# withcc3200.net
KiCad netlist of a schematic drawn in EAGLE
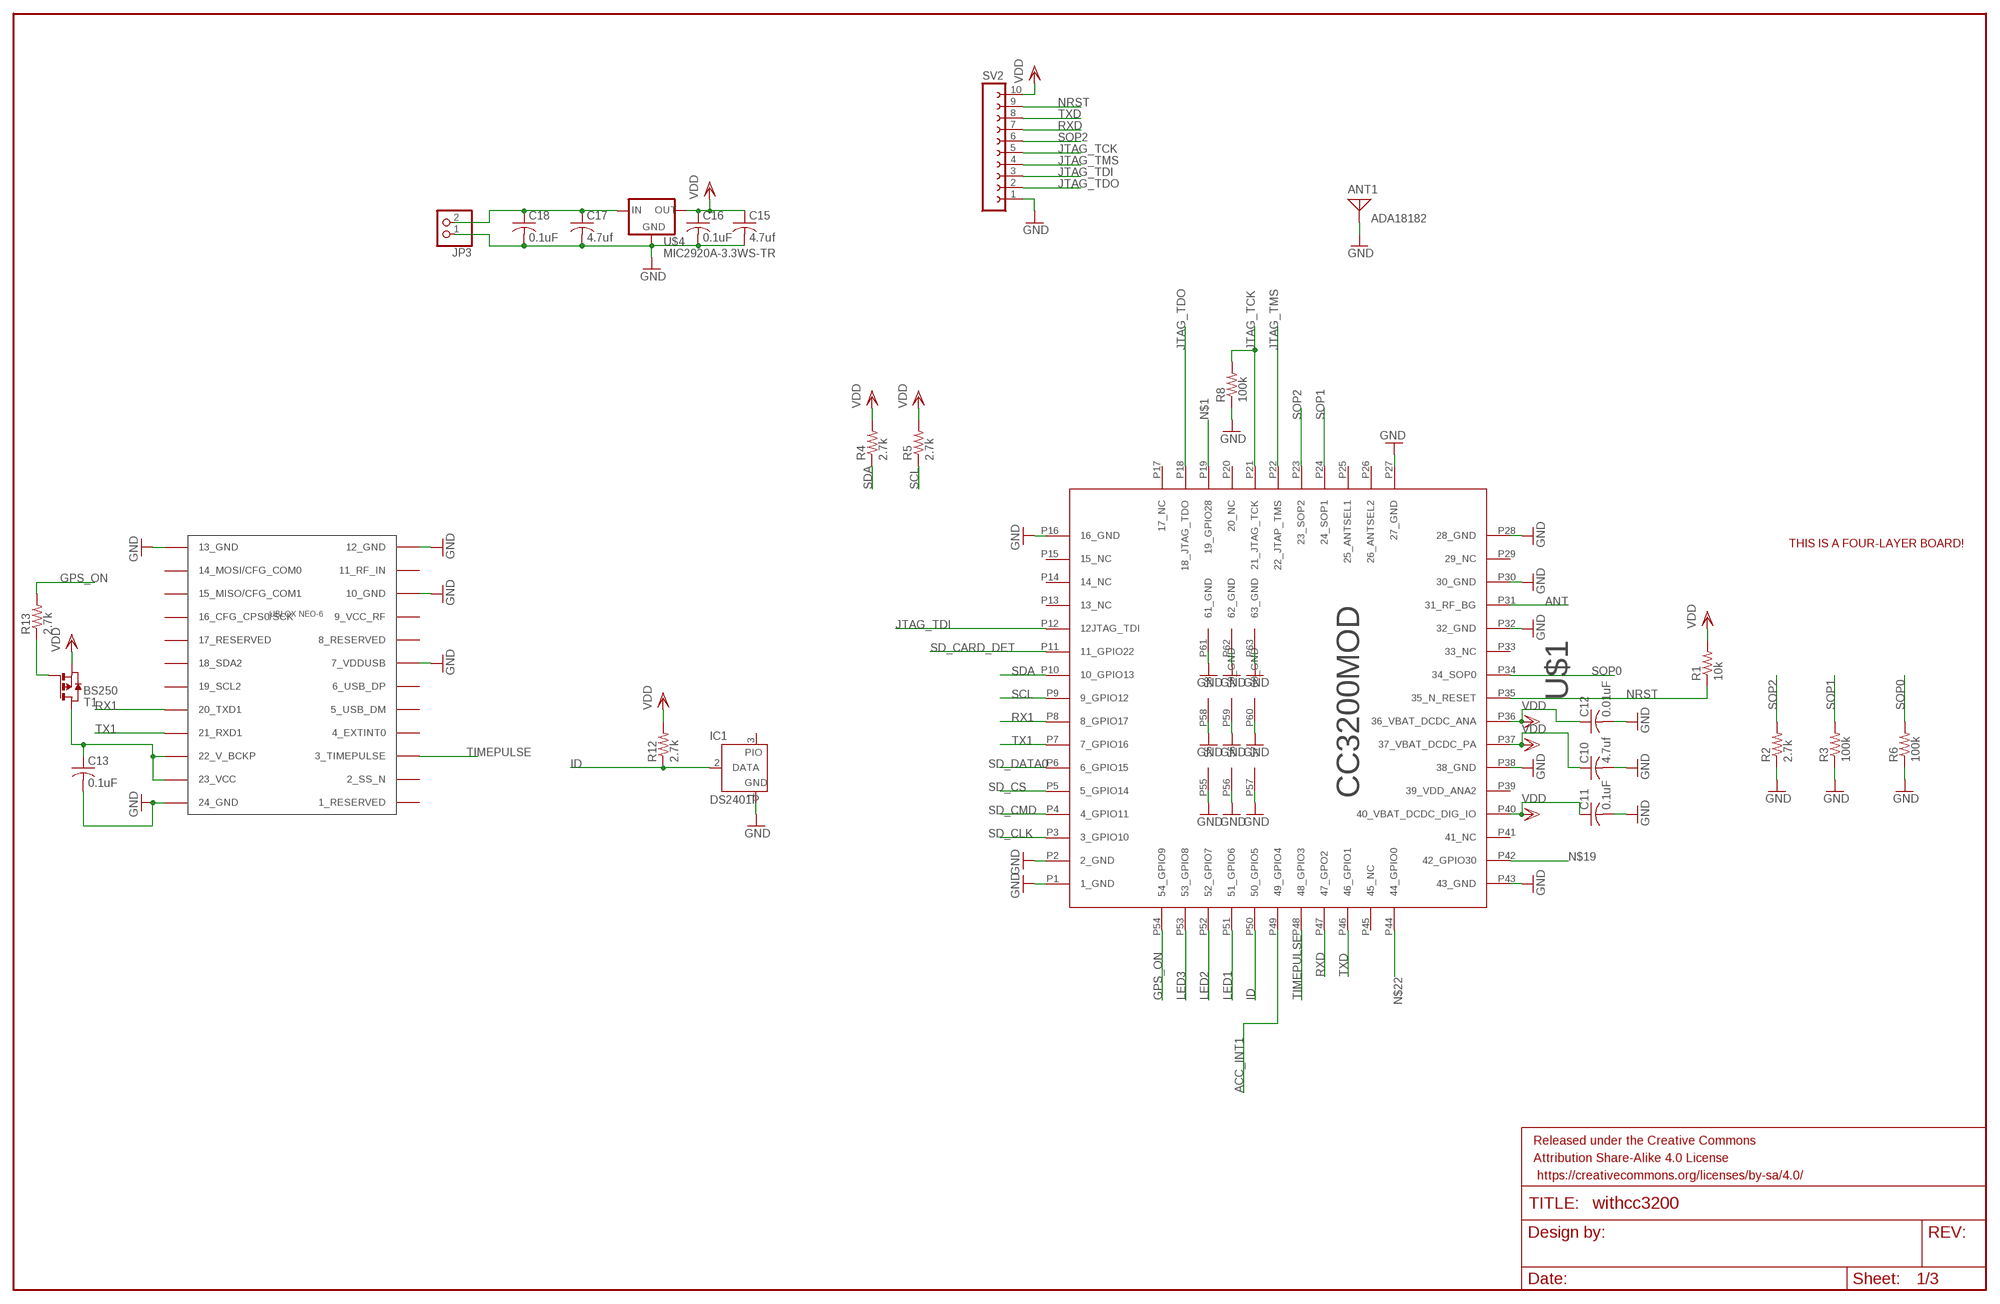
[diagram p0: schematic, sheet 1]
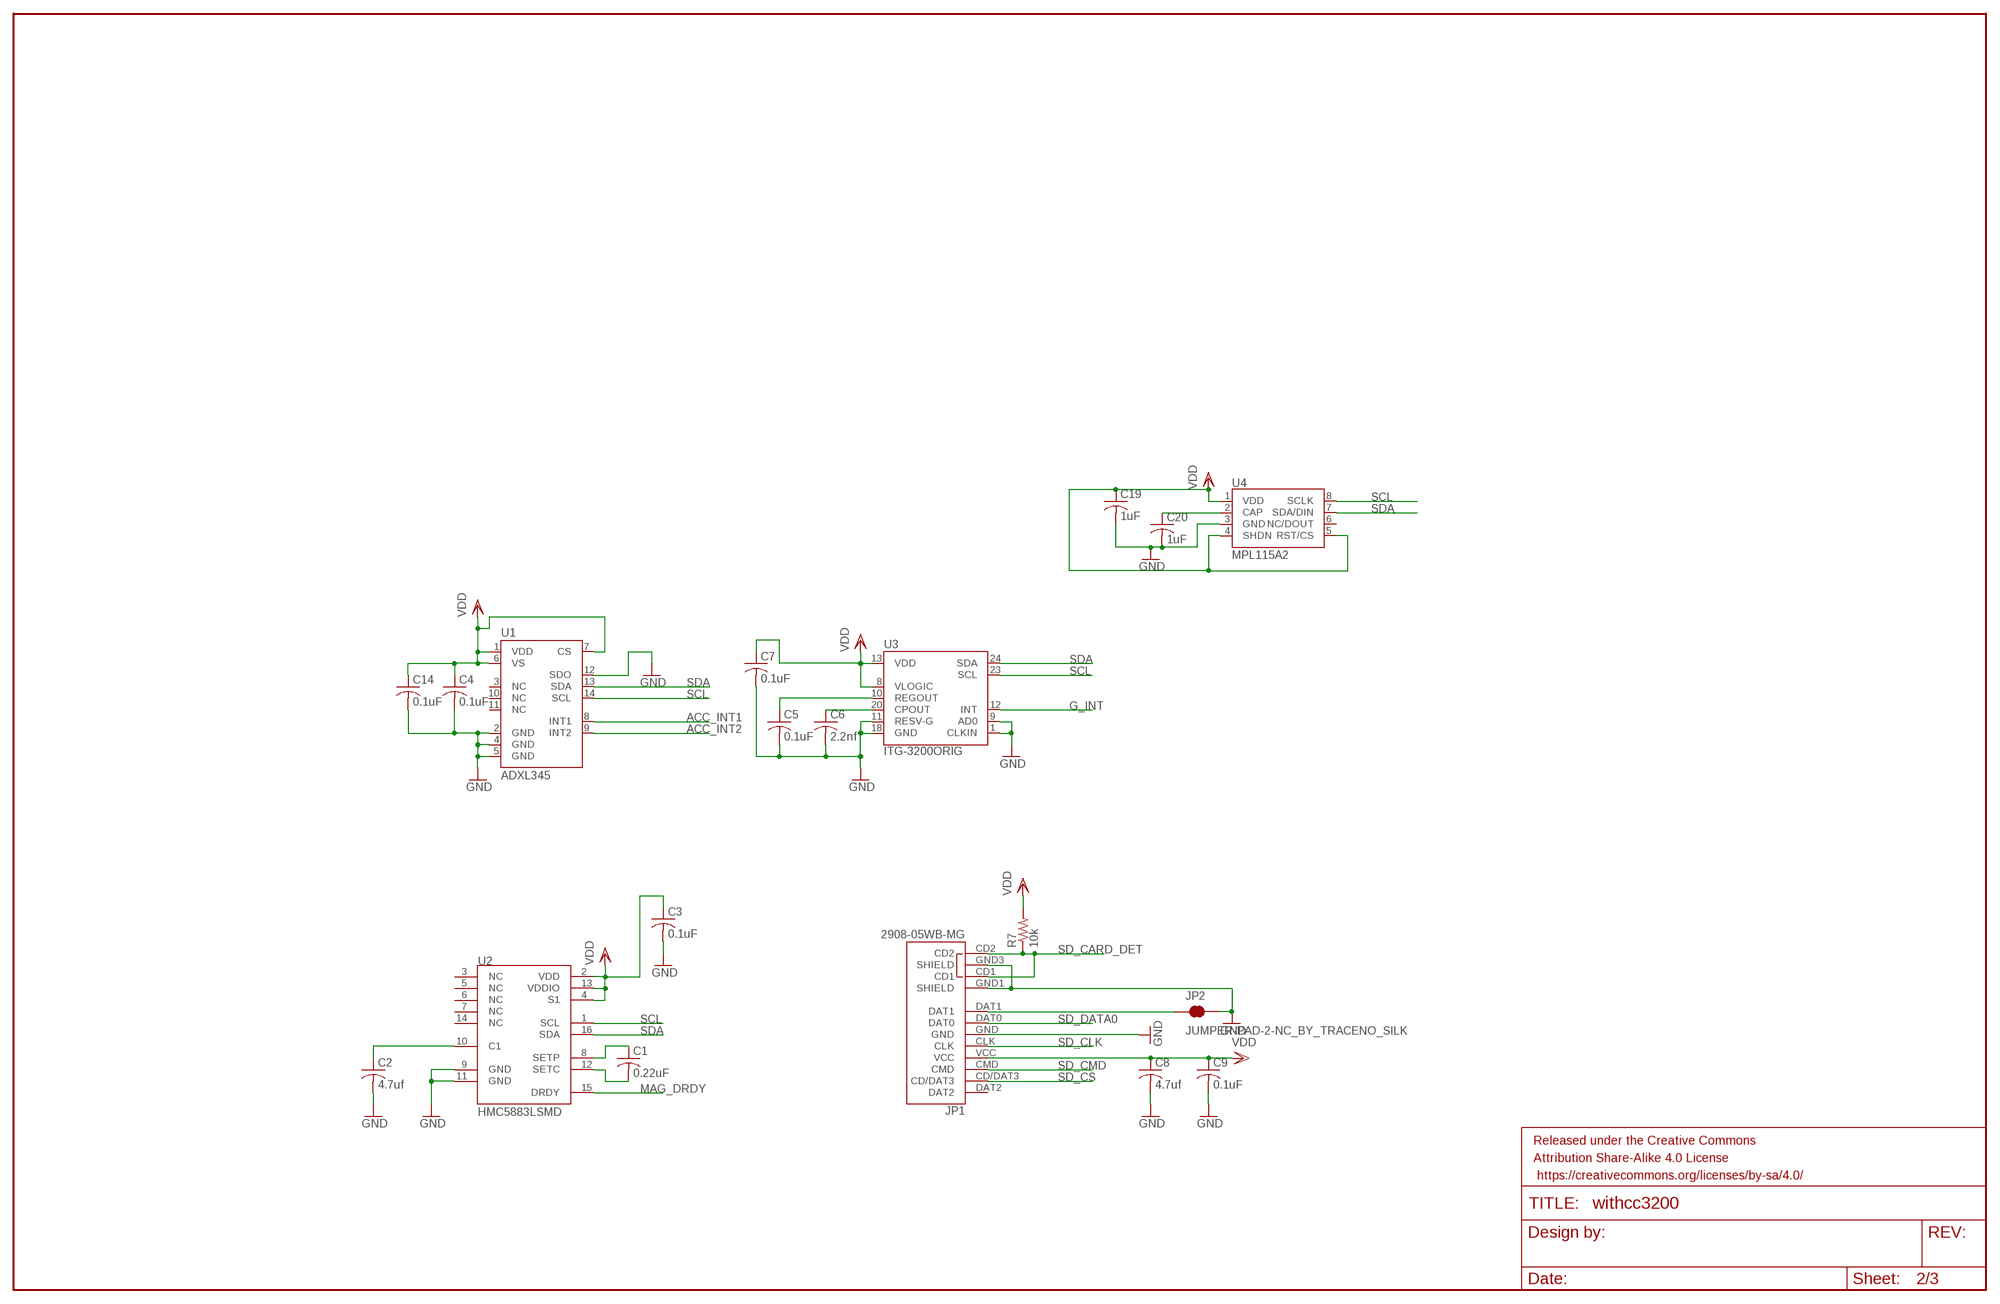
[diagram p1: schematic, sheet 2]
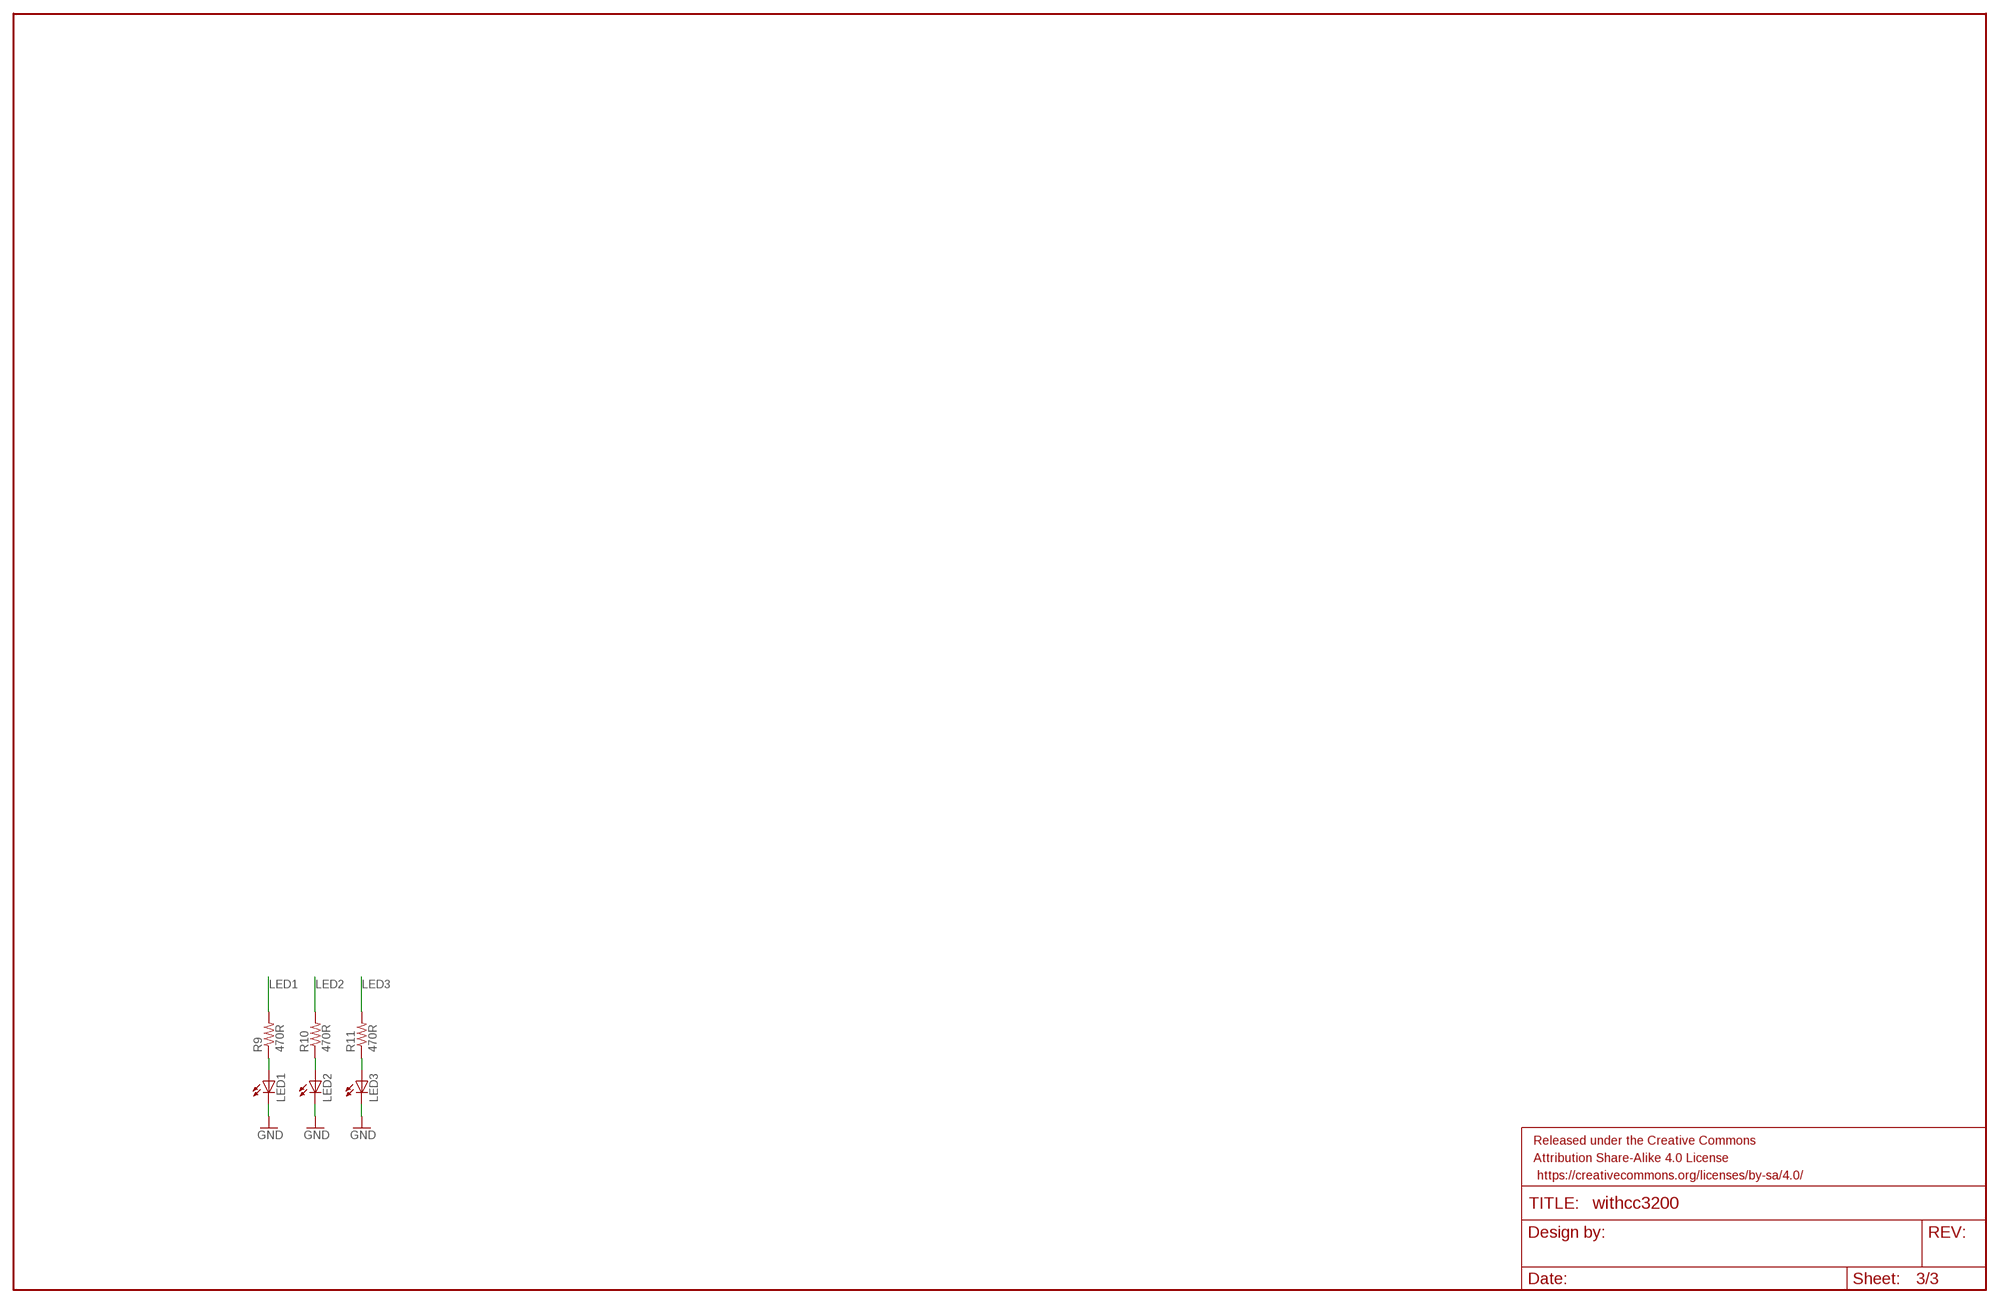
[diagram p2: schematic, sheet 3]

(export (version "E")
  (design (tool "Eeschema 10.0.6"))
  (components
    (comp (ref "C1")
      (value "0.22uF")
      (footprint "eagle-import:C0805K")
      (libsource (lib "eagle-import") (part "C-USC0805K"))
    )
    (comp (ref "C2")
      (value "4.7uf")
      (footprint "eagle-import:C0805K")
      (libsource (lib "eagle-import") (part "C-USC0805K"))
    )
    (comp (ref "C3")
      (value "0.1uF")
      (footprint "eagle-import:C0805K")
      (libsource (lib "eagle-import") (part "C-USC0805K"))
    )
    (comp (ref "C4")
      (value "0.1uF")
      (footprint "eagle-import:C0805K")
      (libsource (lib "eagle-import") (part "C-USC0805K"))
    )
    (comp (ref "C5")
      (value "0.1uF")
      (footprint "eagle-import:C0805K")
      (libsource (lib "eagle-import") (part "C-USC0805K"))
    )
    (comp (ref "C6")
      (value "2.2nf")
      (footprint "eagle-import:C0805K")
      (libsource (lib "eagle-import") (part "C-USC0805K"))
    )
    (comp (ref "C7")
      (value "0.1uF")
      (footprint "eagle-import:C0805K")
      (libsource (lib "eagle-import") (part "C-USC0805K"))
    )
    (comp (ref "C8")
      (value "4.7uf")
      (footprint "eagle-import:C0805K")
      (libsource (lib "eagle-import") (part "C-USC0805K"))
    )
    (comp (ref "C9")
      (value "0.1uF")
      (footprint "eagle-import:C0805K")
      (libsource (lib "eagle-import") (part "C-USC0805K"))
    )
    (comp (ref "C14")
      (value "0.1uF")
      (footprint "eagle-import:C0805K")
      (libsource (lib "eagle-import") (part "C-USC0805K"))
    )
    (comp (ref "C19")
      (value "1uF")
      (footprint "eagle-import:C0805K")
      (libsource (lib "eagle-import") (part "C-USC0805K"))
    )
    (comp (ref "C20")
      (value "1uF")
      (footprint "eagle-import:C0805K")
      (libsource (lib "eagle-import") (part "C-USC0805K"))
    )
    (comp (ref "FRAME2")
      (value "FRAME-LEDGER")
      (footprint "eagle-import:CREATIVE_COMMONS")
      (libsource (lib "eagle-import") (part "FRAME-LEDGER"))
    )
    (comp (ref "JP1")
      (value "2908-05WB-MG")
      (footprint "eagle-import:MICRO-SD-SOCKET-SDIO")
      (libsource (lib "eagle-import") (part "USD-SDIO-SOCKET"))
    )
    (comp (ref "JP2")
      (value "JUMPER-PAD-2-NC_BY_TRACENO_SILK")
      (footprint "eagle-import:PAD-JUMPER-2-NC_BY_TRACE_NO_SILK")
      (libsource (lib "eagle-import") (part "JUMPER-PAD-2-NC_BY_TRACENO_SILK"))
    )
    (comp (ref "R7")
      (value "10k")
      (footprint "eagle-import:R0603")
      (libsource (lib "eagle-import") (part "R-US_R0603"))
    )
    (comp (ref "U1")
      (value "ADXL345")
      (footprint "eagle-import:LGA14")
      (libsource (lib "eagle-import") (part "ADXL345"))
    )
    (comp (ref "U2")
      (value "HMC5883LSMD")
      (footprint "eagle-import:16LPCC")
      (libsource (lib "eagle-import") (part "HMC5883LSMD"))
    )
    (comp (ref "U3")
      (value "ITG-3200ORIG")
      (footprint "eagle-import:QFN-24")
      (libsource (lib "eagle-import") (part "ITG-3200ORIG"))
    )
    (comp (ref "U4")
      (value "MPL115A2")
      (footprint "eagle-import:LGA8")
      (libsource (lib "eagle-import") (part "MPL115A"))
    )
    (comp (ref "FRAME3")
      (value "FRAME-LEDGER")
      (footprint "eagle-import:CREATIVE_COMMONS")
      (libsource (lib "eagle-import") (part "FRAME-LEDGER"))
    )
    (comp (ref "LED1")
      (value "LEDCHIPLED_0805")
      (footprint "eagle-import:CHIPLED_0805")
      (libsource (lib "eagle-import") (part "LEDCHIPLED_0805"))
    )
    (comp (ref "LED2")
      (value "LEDCHIPLED_0805")
      (footprint "eagle-import:CHIPLED_0805")
      (libsource (lib "eagle-import") (part "LEDCHIPLED_0805"))
    )
    (comp (ref "LED3")
      (value "LEDCHIPLED_0805")
      (footprint "eagle-import:CHIPLED_0805")
      (libsource (lib "eagle-import") (part "LEDCHIPLED_0805"))
    )
    (comp (ref "R9")
      (value "470R")
      (footprint "eagle-import:R0603")
      (libsource (lib "eagle-import") (part "R-US_R0603"))
    )
    (comp (ref "R10")
      (value "470R")
      (footprint "eagle-import:R0603")
      (libsource (lib "eagle-import") (part "R-US_R0603"))
    )
    (comp (ref "R11")
      (value "470R")
      (footprint "eagle-import:R0603")
      (libsource (lib "eagle-import") (part "R-US_R0603"))
    )
    (comp (ref "ANT1")
      (value "ADA18182")
      (footprint "eagle-import:PAD-01")
      (libsource (lib "eagle-import") (part "ANTENNA"))
    )
    (comp (ref "C10")
      (value "4.7uf")
      (footprint "eagle-import:C0805K")
      (libsource (lib "eagle-import") (part "C-USC0805K"))
    )
    (comp (ref "C11")
      (value "0.1uF")
      (footprint "eagle-import:C0805K")
      (libsource (lib "eagle-import") (part "C-USC0805K"))
    )
    (comp (ref "C12")
      (value "0.01uF")
      (footprint "eagle-import:C0805K")
      (libsource (lib "eagle-import") (part "C-USC0805K"))
    )
    (comp (ref "C13")
      (value "0.1uF")
      (footprint "eagle-import:C0805K")
      (libsource (lib "eagle-import") (part "C-USC0805K"))
    )
    (comp (ref "C15")
      (value "4.7uf")
      (footprint "eagle-import:C0805K")
      (libsource (lib "eagle-import") (part "C-USC0805K"))
    )
    (comp (ref "C16")
      (value "0.1uF")
      (footprint "eagle-import:C0805K")
      (libsource (lib "eagle-import") (part "C-USC0805K"))
    )
    (comp (ref "C17")
      (value "4.7uf")
      (footprint "eagle-import:C0805K")
      (libsource (lib "eagle-import") (part "C-USC0805K"))
    )
    (comp (ref "C18")
      (value "0.1uF")
      (footprint "eagle-import:C0805K")
      (libsource (lib "eagle-import") (part "C-USC0805K"))
    )
    (comp (ref "FRAME1")
      (value "FRAME-LEDGER")
      (footprint "eagle-import:CREATIVE_COMMONS")
      (libsource (lib "eagle-import") (part "FRAME-LEDGER"))
    )
    (comp (ref "IC1")
      (value "DS2401P")
      (footprint "eagle-import:TSOC6")
      (libsource (lib "eagle-import") (part "DS2405P"))
    )
    (comp (ref "JP3")
      (value "PINHD-1X2")
      (footprint "eagle-import:1X02")
      (libsource (lib "eagle-import") (part "PINHD-1X2"))
    )
    (comp (ref "R1")
      (value "10k")
      (footprint "eagle-import:R0603")
      (libsource (lib "eagle-import") (part "R-US_R0603"))
    )
    (comp (ref "R2")
      (value "2.7k")
      (footprint "eagle-import:R0603")
      (libsource (lib "eagle-import") (part "R-US_R0603"))
    )
    (comp (ref "R3")
      (value "100k")
      (footprint "eagle-import:R0603")
      (libsource (lib "eagle-import") (part "R-US_R0603"))
    )
    (comp (ref "R4")
      (value "2.7k")
      (footprint "eagle-import:R0603")
      (libsource (lib "eagle-import") (part "R-US_R0603"))
    )
    (comp (ref "R5")
      (value "2.7k")
      (footprint "eagle-import:R0603")
      (libsource (lib "eagle-import") (part "R-US_R0603"))
    )
    (comp (ref "R6")
      (value "100k")
      (footprint "eagle-import:R0603")
      (libsource (lib "eagle-import") (part "R-US_R0603"))
    )
    (comp (ref "R8")
      (value "100k")
      (footprint "eagle-import:R0603")
      (libsource (lib "eagle-import") (part "R-US_R0603"))
    )
    (comp (ref "R12")
      (value "2.7k")
      (footprint "eagle-import:R0603")
      (libsource (lib "eagle-import") (part "R-US_R0603"))
    )
    (comp (ref "R13")
      (value "2.7k")
      (footprint "eagle-import:R0603")
      (libsource (lib "eagle-import") (part "R-US_R0603"))
    )
    (comp (ref "SV2")
      (value "FE10-1")
      (footprint "eagle-import:FE10")
      (libsource (lib "eagle-import") (part "FE10-1"))
    )
    (comp (ref "T1")
      (value "BS250")
      (footprint "eagle-import:SOT-23")
      (libsource (lib "eagle-import") (part "PMOSSOT23"))
    )
    (comp (ref "U$1")
      (value "CC3200MOD")
      (footprint "eagle-import:CC3200MOD")
      (libsource (lib "eagle-import") (part "CC3200"))
    )
    (comp (ref "U$2")
      (value "UBLOX_NEO-7")
      (footprint "eagle-import:UBLOX_NEO-6P")
      (libsource (lib "eagle-import") (part "UBLOX_NEO-6"))
    )
    (comp (ref "U$3")
      (value "FOUR_LAYER_WARNING")
      (footprint "eagle-import:FOUR_LAYER_WARNING")
      (libsource (lib "eagle-import") (part "FOUR_LAYER_WARNING"))
    )
    (comp (ref "U$4")
      (value "MIC2920A-3.3WS-TR")
      (footprint "eagle-import:SOT223")
      (libsource (lib "eagle-import") (part "V_REG_MIC2920"))
    )
  )
  (nets
    (net (code "1") (name "ACC_INT1") (class "Default")
      (node (ref "U$1") (pin "P49") (pinfunction "49_GPIO4_P49") (pintype "bidirectional"))
      (node (ref "U1") (pin "8") (pinfunction "INT1_8") (pintype "bidirectional"))
    )
    (net (code "2") (name "ACC_INT2") (class "Default")
      (node (ref "U1") (pin "9") (pinfunction "INT2_9") (pintype "bidirectional"))
    )
    (net (code "3") (name "ANT") (class "Default")
      (node (ref "U$1") (pin "P31") (pinfunction "31_RF_BG_P31") (pintype "bidirectional"))
    )
    (net (code "4") (name "GND") (class "Default")
      (node (ref "ANT1") (pin "1") (pinfunction "1_1") (pintype "output"))
      (node (ref "C10") (pin "2") (pinfunction "2_2") (pintype "passive"))
      (node (ref "C11") (pin "2") (pinfunction "2_2") (pintype "passive"))
      (node (ref "C12") (pin "2") (pinfunction "2_2") (pintype "passive"))
      (node (ref "C13") (pin "2") (pinfunction "2_2") (pintype "passive"))
      (node (ref "C14") (pin "2") (pinfunction "2_2") (pintype "passive"))
      (node (ref "C15") (pin "2") (pinfunction "2_2") (pintype "passive"))
      (node (ref "C16") (pin "2") (pinfunction "2_2") (pintype "passive"))
      (node (ref "C17") (pin "2") (pinfunction "2_2") (pintype "passive"))
      (node (ref "C18") (pin "2") (pinfunction "2_2") (pintype "passive"))
      (node (ref "C19") (pin "2") (pinfunction "2_2") (pintype "passive"))
      (node (ref "C2") (pin "2") (pinfunction "2_2") (pintype "passive"))
      (node (ref "C20") (pin "2") (pinfunction "2_2") (pintype "passive"))
      (node (ref "C3") (pin "2") (pinfunction "2_2") (pintype "passive"))
      (node (ref "C4") (pin "2") (pinfunction "2_2") (pintype "passive"))
      (node (ref "C5") (pin "2") (pinfunction "2_2") (pintype "passive"))
      (node (ref "C6") (pin "2") (pinfunction "2_2") (pintype "passive"))
      (node (ref "C7") (pin "2") (pinfunction "2_2") (pintype "passive"))
      (node (ref "C8") (pin "2") (pinfunction "2_2") (pintype "passive"))
      (node (ref "C9") (pin "2") (pinfunction "2_2") (pintype "passive"))
      (node (ref "IC1") (pin "1") (pinfunction "GND_1") (pintype "passive"))
      (node (ref "JP1") (pin "GND") (pinfunction "GND_GND") (pintype "bidirectional"))
      (node (ref "JP1") (pin "GND1") (pinfunction "SHIELD_GND1") (pintype "bidirectional"))
      (node (ref "JP1") (pin "GND3") (pinfunction "SHIELD_GND3") (pintype "bidirectional"))
      (node (ref "JP2") (pin "2") (pinfunction "2_2") (pintype "passive"))
      (node (ref "JP3") (pin "1") (pinfunction "1_1") (pintype "passive"))
      (node (ref "LED1") (pin "C") (pinfunction "C_C") (pintype "passive"))
      (node (ref "LED2") (pin "C") (pinfunction "C_C") (pintype "passive"))
      (node (ref "LED3") (pin "C") (pinfunction "C_C") (pintype "passive"))
      (node (ref "R2") (pin "1") (pinfunction "1_1") (pintype "passive"))
      (node (ref "R3") (pin "1") (pinfunction "1_1") (pintype "passive"))
      (node (ref "R6") (pin "1") (pinfunction "1_1") (pintype "passive"))
      (node (ref "R8") (pin "1") (pinfunction "1_1") (pintype "passive"))
      (node (ref "SV2") (pin "1") (pinfunction "1_1") (pintype "passive"))
      (node (ref "U$1") (pin "P1") (pinfunction "1_GND_P1") (pintype "bidirectional"))
      (node (ref "U$1") (pin "P16") (pinfunction "16_GND_P16") (pintype "bidirectional"))
      (node (ref "U$1") (pin "P2") (pinfunction "2_GND_P2") (pintype "bidirectional"))
      (node (ref "U$1") (pin "P27") (pinfunction "27_GND_P27") (pintype "bidirectional"))
      (node (ref "U$1") (pin "P28") (pinfunction "28_GND_P28") (pintype "bidirectional"))
      (node (ref "U$1") (pin "P30") (pinfunction "30_GND_P30") (pintype "bidirectional"))
      (node (ref "U$1") (pin "P32") (pinfunction "32_GND_P32") (pintype "bidirectional"))
      (node (ref "U$1") (pin "P38") (pinfunction "38_GND_P38") (pintype "bidirectional"))
      (node (ref "U$1") (pin "P43") (pinfunction "43_GND_P43") (pintype "bidirectional"))
      (node (ref "U$1") (pin "P55") (pinfunction "55_P55") (pintype "bidirectional"))
      (node (ref "U$1") (pin "P56") (pinfunction "56_P56") (pintype "bidirectional"))
      (node (ref "U$1") (pin "P57") (pinfunction "57_P57") (pintype "bidirectional"))
      (node (ref "U$1") (pin "P58") (pinfunction "58_P58") (pintype "bidirectional"))
      (node (ref "U$1") (pin "P59") (pinfunction "59_GND_P59") (pintype "bidirectional"))
      (node (ref "U$1") (pin "P60") (pinfunction "60_GND_P60") (pintype "bidirectional"))
      (node (ref "U$1") (pin "P61") (pinfunction "61_GND_P61") (pintype "bidirectional"))
      (node (ref "U$1") (pin "P62") (pinfunction "62_GND_P62") (pintype "bidirectional"))
      (node (ref "U$1") (pin "P63") (pinfunction "63_GND_P63") (pintype "bidirectional"))
      (node (ref "U$2") (pin "10_GND") (pinfunction "10_GND_10_GND") (pintype "bidirectional"))
      (node (ref "U$2") (pin "12_GND") (pinfunction "12_GND_12_GND") (pintype "bidirectional"))
      (node (ref "U$2") (pin "13_GND") (pinfunction "13_GND_13_GND") (pintype "bidirectional"))
      (node (ref "U$2") (pin "24_GND") (pinfunction "24_GND_24_GND") (pintype "bidirectional"))
      (node (ref "U$2") (pin "7_VDDUSB") (pinfunction "7_VDDUSB_7_VDDUSB") (pintype "bidirectional"))
      (node (ref "U$4") (pin "2") (pinfunction "GND_2") (pintype "input"))
      (node (ref "U1") (pin "12") (pinfunction "SDO_12") (pintype "bidirectional"))
      (node (ref "U1") (pin "2") (pinfunction "GND_2") (pintype "bidirectional"))
      (node (ref "U1") (pin "4") (pinfunction "GND_4") (pintype "bidirectional"))
      (node (ref "U1") (pin "5") (pinfunction "GND_5") (pintype "bidirectional"))
      (node (ref "U2") (pin "11") (pinfunction "GND_11") (pintype "bidirectional"))
      (node (ref "U2") (pin "9") (pinfunction "GND_9") (pintype "bidirectional"))
      (node (ref "U3") (pin "1") (pinfunction "CLKIN_1") (pintype "bidirectional"))
      (node (ref "U3") (pin "11") (pinfunction "RESV-G_11") (pintype "bidirectional"))
      (node (ref "U3") (pin "18") (pinfunction "GND_18") (pintype "bidirectional"))
      (node (ref "U3") (pin "9") (pinfunction "AD0_9") (pintype "bidirectional"))
      (node (ref "U4") (pin "3") (pinfunction "GND_3") (pintype "bidirectional"))
    )
    (net (code "5") (name "GPS_ON") (class "Default")
      (node (ref "R13") (pin "2") (pinfunction "2_2") (pintype "passive"))
      (node (ref "U$1") (pin "P54") (pinfunction "54_GPIO9_P54") (pintype "bidirectional"))
    )
    (net (code "6") (name "G_INT") (class "Default")
      (node (ref "U3") (pin "12") (pinfunction "INT_12") (pintype "bidirectional"))
    )
    (net (code "7") (name "ID") (class "Default")
      (node (ref "IC1") (pin "2") (pinfunction "DATA_2") (pintype "input"))
      (node (ref "R12") (pin "1") (pinfunction "1_1") (pintype "passive"))
      (node (ref "U$1") (pin "P50") (pinfunction "50_GPIO5_P50") (pintype "bidirectional"))
    )
    (net (code "8") (name "JTAG_TCK") (class "Default")
      (node (ref "R8") (pin "2") (pinfunction "2_2") (pintype "passive"))
      (node (ref "SV2") (pin "5") (pinfunction "5_5") (pintype "passive"))
      (node (ref "U$1") (pin "P21") (pinfunction "21_JTAG_TCK_P21") (pintype "bidirectional"))
    )
    (net (code "9") (name "JTAG_TDI") (class "Default")
      (node (ref "SV2") (pin "3") (pinfunction "3_3") (pintype "passive"))
      (node (ref "U$1") (pin "P12") (pinfunction "12JTAG_TDI_P12") (pintype "bidirectional"))
    )
    (net (code "10") (name "JTAG_TDO") (class "Default")
      (node (ref "SV2") (pin "2") (pinfunction "2_2") (pintype "passive"))
      (node (ref "U$1") (pin "P18") (pinfunction "18_JTAG_TDO_P18") (pintype "bidirectional"))
    )
    (net (code "11") (name "JTAG_TMS") (class "Default")
      (node (ref "SV2") (pin "4") (pinfunction "4_4") (pintype "passive"))
      (node (ref "U$1") (pin "P22") (pinfunction "22_JTAP_TMS_P22") (pintype "bidirectional"))
    )
    (net (code "12") (name "LED1") (class "Default")
      (node (ref "R9") (pin "2") (pinfunction "2_2") (pintype "passive"))
      (node (ref "U$1") (pin "P51") (pinfunction "51_GPIO6_P51") (pintype "bidirectional"))
    )
    (net (code "13") (name "LED2") (class "Default")
      (node (ref "R10") (pin "2") (pinfunction "2_2") (pintype "passive"))
      (node (ref "U$1") (pin "P52") (pinfunction "52_GPIO7_P52") (pintype "bidirectional"))
    )
    (net (code "14") (name "LED3") (class "Default")
      (node (ref "R11") (pin "2") (pinfunction "2_2") (pintype "passive"))
      (node (ref "U$1") (pin "P53") (pinfunction "53_GPIO8_P53") (pintype "bidirectional"))
    )
    (net (code "15") (name "MAG_DRDY") (class "Default")
      (node (ref "U2") (pin "15") (pinfunction "DRDY_15") (pintype "bidirectional"))
    )
    (net (code "16") (name "N$1") (class "Default")
      (node (ref "U$1") (pin "P19") (pinfunction "19_GPIO28_P19") (pintype "bidirectional"))
    )
    (net (code "17") (name "N$19") (class "Default")
      (node (ref "U$1") (pin "P42") (pinfunction "42_GPIO30_P42") (pintype "bidirectional"))
    )
    (net (code "18") (name "N$22") (class "Default")
      (node (ref "U$1") (pin "P44") (pinfunction "44_GPIO0_P44") (pintype "bidirectional"))
    )
    (net (code "19") (name "NRST") (class "Default")
      (node (ref "R1") (pin "1") (pinfunction "1_1") (pintype "passive"))
      (node (ref "SV2") (pin "9") (pinfunction "9_9") (pintype "passive"))
      (node (ref "U$1") (pin "P35") (pinfunction "35_N_RESET_P35") (pintype "bidirectional"))
    )
    (net (code "20") (name "Net-(JP1-PadDAT1)") (class "Default")
      (node (ref "JP1") (pin "DAT1") (pinfunction "DAT1_DAT1") (pintype "bidirectional"))
      (node (ref "JP2") (pin "1") (pinfunction "1_1") (pintype "passive"))
    )
    (net (code "21") (name "Net-(LED1-PadA)") (class "Default")
      (node (ref "LED1") (pin "A") (pinfunction "A_A") (pintype "passive"))
      (node (ref "R9") (pin "1") (pinfunction "1_1") (pintype "passive"))
    )
    (net (code "22") (name "Net-(LED2-PadA)") (class "Default")
      (node (ref "LED2") (pin "A") (pinfunction "A_A") (pintype "passive"))
      (node (ref "R10") (pin "1") (pinfunction "1_1") (pintype "passive"))
    )
    (net (code "23") (name "Net-(LED3-PadA)") (class "Default")
      (node (ref "LED3") (pin "A") (pinfunction "A_A") (pintype "passive"))
      (node (ref "R11") (pin "1") (pinfunction "1_1") (pintype "passive"))
    )
    (net (code "24") (name "Net-(T1-D)") (class "Default")
      (node (ref "C13") (pin "1") (pinfunction "1_1") (pintype "passive"))
      (node (ref "T1") (pin "1") (pinfunction "D_1") (pintype "passive"))
      (node (ref "U$2") (pin "22_V_BCKP") (pinfunction "22_V_BCKP_22_V_BCKP") (pintype "bidirectional"))
      (node (ref "U$2") (pin "23_VCC") (pinfunction "23_VCC_23_VCC") (pintype "bidirectional"))
    )
    (net (code "25") (name "Net-(T1-G)") (class "Default")
      (node (ref "R13") (pin "1") (pinfunction "1_1") (pintype "passive"))
      (node (ref "T1") (pin "3") (pinfunction "G_3") (pintype "passive"))
    )
    (net (code "26") (name "Net-(U$4-IN)") (class "Default")
      (node (ref "C17") (pin "1") (pinfunction "1_1") (pintype "passive"))
      (node (ref "C18") (pin "1") (pinfunction "1_1") (pintype "passive"))
      (node (ref "JP3") (pin "2") (pinfunction "2_2") (pintype "passive"))
      (node (ref "U$4") (pin "1") (pinfunction "IN_1") (pintype "input"))
    )
    (net (code "27") (name "Net-(U2-C1)") (class "Default")
      (node (ref "C2") (pin "1") (pinfunction "1_1") (pintype "passive"))
      (node (ref "U2") (pin "10") (pinfunction "C1_10") (pintype "bidirectional"))
    )
    (net (code "28") (name "Net-(U2-SETC)") (class "Default")
      (node (ref "C1") (pin "2") (pinfunction "2_2") (pintype "passive"))
      (node (ref "U2") (pin "12") (pinfunction "SETC_12") (pintype "bidirectional"))
    )
    (net (code "29") (name "Net-(U2-SETP)") (class "Default")
      (node (ref "C1") (pin "1") (pinfunction "1_1") (pintype "passive"))
      (node (ref "U2") (pin "8") (pinfunction "SETP_8") (pintype "bidirectional"))
    )
    (net (code "30") (name "Net-(U3-CPOUT)") (class "Default")
      (node (ref "C6") (pin "1") (pinfunction "1_1") (pintype "passive"))
      (node (ref "U3") (pin "20") (pinfunction "CPOUT_20") (pintype "bidirectional"))
    )
    (net (code "31") (name "Net-(U3-REGOUT)") (class "Default")
      (node (ref "C5") (pin "1") (pinfunction "1_1") (pintype "passive"))
      (node (ref "U3") (pin "10") (pinfunction "REGOUT_10") (pintype "bidirectional"))
    )
    (net (code "32") (name "Net-(U4-CAP)") (class "Default")
      (node (ref "C20") (pin "1") (pinfunction "1_1") (pintype "passive"))
      (node (ref "U4") (pin "2") (pinfunction "CAP_2") (pintype "bidirectional"))
    )
    (net (code "33") (name "RX1") (class "Default")
      (node (ref "U$1") (pin "P8") (pinfunction "8_GPIO17_P8") (pintype "bidirectional"))
      (node (ref "U$2") (pin "20_TXD1") (pinfunction "20_TXD1_20_TXD1") (pintype "bidirectional"))
    )
    (net (code "34") (name "RXD") (class "Default")
      (node (ref "SV2") (pin "7") (pinfunction "7_7") (pintype "passive"))
      (node (ref "U$1") (pin "P47") (pinfunction "47_GPO2_P47") (pintype "bidirectional"))
    )
    (net (code "35") (name "SCL") (class "Default")
      (node (ref "R5") (pin "1") (pinfunction "1_1") (pintype "passive"))
      (node (ref "U$1") (pin "P9") (pinfunction "9_GPIO12_P9") (pintype "bidirectional"))
      (node (ref "U1") (pin "14") (pinfunction "SCL_14") (pintype "bidirectional"))
      (node (ref "U2") (pin "1") (pinfunction "SCL_1") (pintype "bidirectional"))
      (node (ref "U3") (pin "23") (pinfunction "SCL_23") (pintype "bidirectional"))
      (node (ref "U4") (pin "8") (pinfunction "SCLK_8") (pintype "bidirectional"))
    )
    (net (code "36") (name "SDA") (class "Default")
      (node (ref "R4") (pin "1") (pinfunction "1_1") (pintype "passive"))
      (node (ref "U$1") (pin "P10") (pinfunction "10_GPIO13_P10") (pintype "bidirectional"))
      (node (ref "U1") (pin "13") (pinfunction "SDA_13") (pintype "bidirectional"))
      (node (ref "U2") (pin "16") (pinfunction "SDA_16") (pintype "bidirectional"))
      (node (ref "U3") (pin "24") (pinfunction "SDA_24") (pintype "bidirectional"))
      (node (ref "U4") (pin "7") (pinfunction "SDA/DIN_7") (pintype "bidirectional"))
    )
    (net (code "37") (name "SD_CARD_DET") (class "Default")
      (node (ref "JP1") (pin "CD1") (pinfunction "CD1_CD1") (pintype "bidirectional"))
      (node (ref "JP1") (pin "CD2") (pinfunction "CD2_CD2") (pintype "bidirectional"))
      (node (ref "R7") (pin "1") (pinfunction "1_1") (pintype "passive"))
      (node (ref "U$1") (pin "P11") (pinfunction "11_GPIO22_P11") (pintype "bidirectional"))
    )
    (net (code "38") (name "SD_CLK") (class "Default")
      (node (ref "JP1") (pin "CLK") (pinfunction "CLK_CLK") (pintype "bidirectional"))
      (node (ref "U$1") (pin "P3") (pinfunction "3_GPIO10_P3") (pintype "bidirectional"))
    )
    (net (code "39") (name "SD_CMD") (class "Default")
      (node (ref "JP1") (pin "CMD") (pinfunction "CMD_CMD") (pintype "bidirectional"))
      (node (ref "U$1") (pin "P4") (pinfunction "4_GPIO11_P4") (pintype "bidirectional"))
    )
    (net (code "40") (name "SD_CS") (class "Default")
      (node (ref "JP1") (pin "CD/DAT3") (pinfunction "CD/DAT3_CD/DAT3") (pintype "bidirectional"))
      (node (ref "U$1") (pin "P5") (pinfunction "5_GPIO14_P5") (pintype "bidirectional"))
    )
    (net (code "41") (name "SD_DATA0") (class "Default")
      (node (ref "JP1") (pin "DAT0") (pinfunction "DAT0_DAT0") (pintype "bidirectional"))
      (node (ref "U$1") (pin "P6") (pinfunction "6_GPIO15_P6") (pintype "bidirectional"))
    )
    (net (code "42") (name "SOP0") (class "Default")
      (node (ref "R6") (pin "2") (pinfunction "2_2") (pintype "passive"))
      (node (ref "U$1") (pin "P34") (pinfunction "34_SOP0_P34") (pintype "bidirectional"))
    )
    (net (code "43") (name "SOP1") (class "Default")
      (node (ref "R3") (pin "2") (pinfunction "2_2") (pintype "passive"))
      (node (ref "U$1") (pin "P24") (pinfunction "24_SOP1_P24") (pintype "bidirectional"))
    )
    (net (code "44") (name "SOP2") (class "Default")
      (node (ref "R2") (pin "2") (pinfunction "2_2") (pintype "passive"))
      (node (ref "SV2") (pin "6") (pinfunction "6_6") (pintype "passive"))
      (node (ref "U$1") (pin "P23") (pinfunction "23_SOP2_P23") (pintype "bidirectional"))
    )
    (net (code "45") (name "TIMEPULSE") (class "Default")
      (node (ref "U$1") (pin "P48") (pinfunction "48_GPIO3_P48") (pintype "bidirectional"))
      (node (ref "U$2") (pin "3_TIMEPULSE") (pinfunction "3_TIMEPULSE_3_TIMEPULSE") (pintype "bidirectional"))
    )
    (net (code "46") (name "TX1") (class "Default")
      (node (ref "U$1") (pin "P7") (pinfunction "7_GPIO16_P7") (pintype "bidirectional"))
      (node (ref "U$2") (pin "21_RXD1") (pinfunction "21_RXD1_21_RXD1") (pintype "bidirectional"))
    )
    (net (code "47") (name "TXD") (class "Default")
      (node (ref "SV2") (pin "8") (pinfunction "8_8") (pintype "passive"))
      (node (ref "U$1") (pin "P46") (pinfunction "46_GPIO1_P46") (pintype "bidirectional"))
    )
    (net (code "48") (name "VDD") (class "Default")
      (node (ref "C10") (pin "1") (pinfunction "1_1") (pintype "passive"))
      (node (ref "C11") (pin "1") (pinfunction "1_1") (pintype "passive"))
      (node (ref "C12") (pin "1") (pinfunction "1_1") (pintype "passive"))
      (node (ref "C14") (pin "1") (pinfunction "1_1") (pintype "passive"))
      (node (ref "C15") (pin "1") (pinfunction "1_1") (pintype "passive"))
      (node (ref "C16") (pin "1") (pinfunction "1_1") (pintype "passive"))
      (node (ref "C19") (pin "1") (pinfunction "1_1") (pintype "passive"))
      (node (ref "C3") (pin "1") (pinfunction "1_1") (pintype "passive"))
      (node (ref "C4") (pin "1") (pinfunction "1_1") (pintype "passive"))
      (node (ref "C7") (pin "1") (pinfunction "1_1") (pintype "passive"))
      (node (ref "C8") (pin "1") (pinfunction "1_1") (pintype "passive"))
      (node (ref "C9") (pin "1") (pinfunction "1_1") (pintype "passive"))
      (node (ref "JP1") (pin "VCC") (pinfunction "VCC_VCC") (pintype "bidirectional"))
      (node (ref "R1") (pin "2") (pinfunction "2_2") (pintype "passive"))
      (node (ref "R12") (pin "2") (pinfunction "2_2") (pintype "passive"))
      (node (ref "R4") (pin "2") (pinfunction "2_2") (pintype "passive"))
      (node (ref "R5") (pin "2") (pinfunction "2_2") (pintype "passive"))
      (node (ref "R7") (pin "2") (pinfunction "2_2") (pintype "passive"))
      (node (ref "SV2") (pin "10") (pinfunction "10_10") (pintype "passive"))
      (node (ref "T1") (pin "2") (pinfunction "S_2") (pintype "passive"))
      (node (ref "U$1") (pin "P36") (pinfunction "36_VBAT_DCDC_ANA_P36") (pintype "bidirectional"))
      (node (ref "U$1") (pin "P37") (pinfunction "37_VBAT_DCDC_PA_P37") (pintype "bidirectional"))
      (node (ref "U$1") (pin "P40") (pinfunction "40_VBAT_DCDC_DIG_IO_P40") (pintype "bidirectional"))
      (node (ref "U$4") (pin "3") (pinfunction "OUT_3") (pintype "passive"))
      (node (ref "U1") (pin "1") (pinfunction "VDD_1") (pintype "bidirectional"))
      (node (ref "U1") (pin "6") (pinfunction "VS_6") (pintype "bidirectional"))
      (node (ref "U1") (pin "7") (pinfunction "CS_7") (pintype "bidirectional"))
      (node (ref "U2") (pin "13") (pinfunction "VDDIO_13") (pintype "bidirectional"))
      (node (ref "U2") (pin "2") (pinfunction "VDD_2") (pintype "bidirectional"))
      (node (ref "U2") (pin "4") (pinfunction "S1_4") (pintype "bidirectional"))
      (node (ref "U3") (pin "13") (pinfunction "VDD_13") (pintype "bidirectional"))
      (node (ref "U3") (pin "8") (pinfunction "VLOGIC_8") (pintype "bidirectional"))
      (node (ref "U4") (pin "1") (pinfunction "VDD_1") (pintype "bidirectional"))
      (node (ref "U4") (pin "4") (pinfunction "SHDN_4") (pintype "bidirectional"))
      (node (ref "U4") (pin "5") (pinfunction "RST/CS_5") (pintype "bidirectional"))
    )
    (net (code "49") (name "unconnected-(IC1-PIO-Pad3)") (class "Default")
      (node (ref "IC1") (pin "3") (pinfunction "PIO_3") (pintype "passive"))
    )
    (net (code "50") (name "unconnected-(JP1-PadDAT2)") (class "Default")
      (node (ref "JP1") (pin "DAT2") (pinfunction "DAT2_DAT2") (pintype "bidirectional"))
    )
    (net (code "51") (name "unconnected-(U$1-13_NC-PadP13)") (class "Default")
      (node (ref "U$1") (pin "P13") (pinfunction "13_NC_P13") (pintype "bidirectional"))
    )
    (net (code "52") (name "unconnected-(U$1-14_NC-PadP14)") (class "Default")
      (node (ref "U$1") (pin "P14") (pinfunction "14_NC_P14") (pintype "bidirectional"))
    )
    (net (code "53") (name "unconnected-(U$1-15_NC-PadP15)") (class "Default")
      (node (ref "U$1") (pin "P15") (pinfunction "15_NC_P15") (pintype "bidirectional"))
    )
    (net (code "54") (name "unconnected-(U$1-17_NC-PadP17)") (class "Default")
      (node (ref "U$1") (pin "P17") (pinfunction "17_NC_P17") (pintype "bidirectional"))
    )
    (net (code "55") (name "unconnected-(U$1-20_NC-PadP20)") (class "Default")
      (node (ref "U$1") (pin "P20") (pinfunction "20_NC_P20") (pintype "bidirectional"))
    )
    (net (code "56") (name "unconnected-(U$1-25_ANTSEL1-PadP25)") (class "Default")
      (node (ref "U$1") (pin "P25") (pinfunction "25_ANTSEL1_P25") (pintype "bidirectional"))
    )
    (net (code "57") (name "unconnected-(U$1-26_ANTSEL2-PadP26)") (class "Default")
      (node (ref "U$1") (pin "P26") (pinfunction "26_ANTSEL2_P26") (pintype "bidirectional"))
    )
    (net (code "58") (name "unconnected-(U$1-29_NC-PadP29)") (class "Default")
      (node (ref "U$1") (pin "P29") (pinfunction "29_NC_P29") (pintype "bidirectional"))
    )
    (net (code "59") (name "unconnected-(U$1-33_NC-PadP33)") (class "Default")
      (node (ref "U$1") (pin "P33") (pinfunction "33_NC_P33") (pintype "bidirectional"))
    )
    (net (code "60") (name "unconnected-(U$1-39_VDD_ANA2-PadP39)") (class "Default")
      (node (ref "U$1") (pin "P39") (pinfunction "39_VDD_ANA2_P39") (pintype "bidirectional"))
    )
    (net (code "61") (name "unconnected-(U$1-41_NC-PadP41)") (class "Default")
      (node (ref "U$1") (pin "P41") (pinfunction "41_NC_P41") (pintype "bidirectional"))
    )
    (net (code "62") (name "unconnected-(U$1-45_NC-PadP45)") (class "Default")
      (node (ref "U$1") (pin "P45") (pinfunction "45_NC_P45") (pintype "bidirectional"))
    )
    (net (code "63") (name "unconnected-(U$2-Pad1_RESERVED)") (class "Default")
      (node (ref "U$2") (pin "1_RESERVED") (pinfunction "1_RESERVED_1_RESERVED") (pintype "bidirectional"))
    )
    (net (code "64") (name "unconnected-(U$2-Pad2_SS_N)") (class "Default")
      (node (ref "U$2") (pin "2_SS_N") (pinfunction "2_SS_N_2_SS_N") (pintype "bidirectional"))
    )
    (net (code "65") (name "unconnected-(U$2-Pad4_EXTINT0)") (class "Default")
      (node (ref "U$2") (pin "4_EXTINT0") (pinfunction "4_EXTINT0_4_EXTINT0") (pintype "bidirectional"))
    )
    (net (code "66") (name "unconnected-(U$2-Pad5_USB_DM)") (class "Default")
      (node (ref "U$2") (pin "5_USB_DM") (pinfunction "5_USB_DM_5_USB_DM") (pintype "bidirectional"))
    )
    (net (code "67") (name "unconnected-(U$2-Pad6_USB_DP)") (class "Default")
      (node (ref "U$2") (pin "6_USB_DP") (pinfunction "6_USB_DP_6_USB_DP") (pintype "bidirectional"))
    )
    (net (code "68") (name "unconnected-(U$2-Pad8_RESERVED)") (class "Default")
      (node (ref "U$2") (pin "8_RESERVED") (pinfunction "8_RESERVED_8_RESERVED") (pintype "bidirectional"))
    )
    (net (code "69") (name "unconnected-(U$2-Pad9_VCC_RF)") (class "Default")
      (node (ref "U$2") (pin "9_VCC_RF") (pinfunction "9_VCC_RF_9_VCC_RF") (pintype "bidirectional"))
    )
    (net (code "70") (name "unconnected-(U$2-Pad11_RF_IN)") (class "Default")
      (node (ref "U$2") (pin "11_RF_IN") (pinfunction "11_RF_IN_11_RF_IN") (pintype "bidirectional"))
    )
    (net (code "71") (name "unconnected-(U$2-Pad14_MOSI{slash}CFG_COM0)") (class "Default")
      (node (ref "U$2") (pin "14_MOSI/CFG_COM0") (pinfunction "14_MOSI/CFG_COM0_14_MOSI/CFG_COM0") (pintype "bidirectional"))
    )
    (net (code "72") (name "unconnected-(U$2-Pad15_MISO{slash}CFG_COM1)") (class "Default")
      (node (ref "U$2") (pin "15_MISO/CFG_COM1") (pinfunction "15_MISO/CFG_COM1_15_MISO/CFG_COM1") (pintype "bidirectional"))
    )
    (net (code "73") (name "unconnected-(U$2-Pad16_CFG_CPS0{slash}SCK)") (class "Default")
      (node (ref "U$2") (pin "16_CFG_CPS0/SCK") (pinfunction "16_CFG_CPS0/SCK_16_CFG_CPS0/SCK") (pintype "bidirectional"))
    )
    (net (code "74") (name "unconnected-(U$2-Pad17_RESERVED)") (class "Default")
      (node (ref "U$2") (pin "17_RESERVED") (pinfunction "17_RESERVED_17_RESERVED") (pintype "bidirectional"))
    )
    (net (code "75") (name "unconnected-(U$2-Pad18_SDA2)") (class "Default")
      (node (ref "U$2") (pin "18_SDA2") (pinfunction "18_SDA2_18_SDA2") (pintype "bidirectional"))
    )
    (net (code "76") (name "unconnected-(U$2-Pad19_SCL2)") (class "Default")
      (node (ref "U$2") (pin "19_SCL2") (pinfunction "19_SCL2_19_SCL2") (pintype "bidirectional"))
    )
    (net (code "77") (name "unconnected-(U1-NC-Pad3)") (class "Default")
      (node (ref "U1") (pin "3") (pinfunction "NC_3") (pintype "bidirectional"))
    )
    (net (code "78") (name "unconnected-(U1-NC-Pad10)") (class "Default")
      (node (ref "U1") (pin "10") (pinfunction "NC_10") (pintype "bidirectional"))
    )
    (net (code "79") (name "unconnected-(U1-NC-Pad11)") (class "Default")
      (node (ref "U1") (pin "11") (pinfunction "NC_11") (pintype "bidirectional"))
    )
    (net (code "80") (name "unconnected-(U2-NC-Pad3)") (class "Default")
      (node (ref "U2") (pin "3") (pinfunction "NC_3") (pintype "bidirectional"))
    )
    (net (code "81") (name "unconnected-(U2-NC-Pad5)") (class "Default")
      (node (ref "U2") (pin "5") (pinfunction "NC_5") (pintype "bidirectional"))
    )
    (net (code "82") (name "unconnected-(U2-NC-Pad6)") (class "Default")
      (node (ref "U2") (pin "6") (pinfunction "NC_6") (pintype "bidirectional"))
    )
    (net (code "83") (name "unconnected-(U2-NC-Pad7)") (class "Default")
      (node (ref "U2") (pin "7") (pinfunction "NC_7") (pintype "bidirectional"))
    )
    (net (code "84") (name "unconnected-(U2-NC-Pad14)") (class "Default")
      (node (ref "U2") (pin "14") (pinfunction "NC_14") (pintype "bidirectional"))
    )
    (net (code "85") (name "unconnected-(U4-NC{slash}DOUT-Pad6)") (class "Default")
      (node (ref "U4") (pin "6") (pinfunction "NC/DOUT_6") (pintype "bidirectional"))
    )
  )
)
